# 5v_power_supply.net
KiCad netlist of a schematic drawn in EAGLE
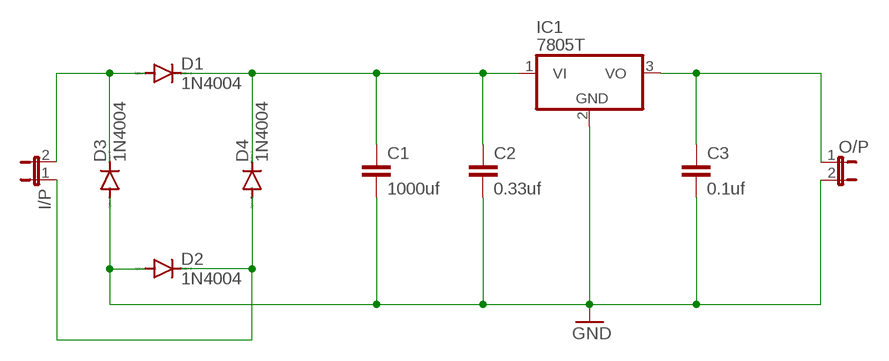
[diagram p0: schematic, sheet 1]

(export (version "E")
  (design (tool "Eeschema 10.0.6"))
  (components
    (comp (ref "C1")
      (value "1000uf")
      (footprint "eagle-import:C2.5-3")
      (libsource (lib "eagle-import") (part "C2,5-3"))
    )
    (comp (ref "C2")
      (value "0.33uf")
      (footprint "eagle-import:C2.5-3")
      (libsource (lib "eagle-import") (part "C2,5-3"))
    )
    (comp (ref "C3")
      (value "0.1uf")
      (footprint "eagle-import:C2.5-3")
      (libsource (lib "eagle-import") (part "C2,5-3"))
    )
    (comp (ref "D1")
      (value "1N4004")
      (footprint "eagle-import:DO41-10")
      (libsource (lib "eagle-import") (part "1N4004"))
    )
    (comp (ref "D2")
      (value "1N4004")
      (footprint "eagle-import:DO41-10")
      (libsource (lib "eagle-import") (part "1N4004"))
    )
    (comp (ref "D3")
      (value "1N4004")
      (footprint "eagle-import:DO41-10")
      (libsource (lib "eagle-import") (part "1N4004"))
    )
    (comp (ref "D4")
      (value "1N4004")
      (footprint "eagle-import:DO41-10")
      (libsource (lib "eagle-import") (part "1N4004"))
    )
    (comp (ref "I/P")
      (value "JP1E")
      (footprint "eagle-import:JP1")
      (libsource (lib "eagle-import") (part "JP1E"))
    )
    (comp (ref "IC1")
      (value "7805T")
      (footprint "eagle-import:TO220H")
      (libsource (lib "eagle-import") (part "78T05"))
    )
    (comp (ref "O/P")
      (value "JP1E")
      (footprint "eagle-import:JP1")
      (libsource (lib "eagle-import") (part "JP1E"))
    )
  )
  (nets
    (net (code "1") (name "GND") (class "Default")
      (node (ref "C1") (pin "2") (pinfunction "2_2") (pintype "passive"))
      (node (ref "C2") (pin "2") (pinfunction "2_2") (pintype "passive"))
      (node (ref "C3") (pin "2") (pinfunction "2_2") (pintype "passive"))
      (node (ref "D2") (pin "A") (pinfunction "A_A") (pintype "passive"))
      (node (ref "D3") (pin "A") (pinfunction "A_A") (pintype "passive"))
      (node (ref "IC1") (pin "2") (pinfunction "GND_2") (pintype "passive"))
      (node (ref "O/P") (pin "2") (pinfunction "2_2") (pintype "passive"))
    )
    (net (code "2") (name "Net-(D1-PadA)") (class "Default")
      (node (ref "D1") (pin "A") (pinfunction "A_A") (pintype "passive"))
      (node (ref "D3") (pin "C") (pinfunction "C_C") (pintype "passive"))
      (node (ref "I/P") (pin "2") (pinfunction "2_2") (pintype "passive"))
    )
    (net (code "3") (name "Net-(D2-PadC)") (class "Default")
      (node (ref "D2") (pin "C") (pinfunction "C_C") (pintype "passive"))
      (node (ref "D4") (pin "A") (pinfunction "A_A") (pintype "passive"))
      (node (ref "I/P") (pin "1") (pinfunction "1_1") (pintype "passive"))
    )
    (net (code "4") (name "Net-(IC1-VI)") (class "Default")
      (node (ref "C1") (pin "1") (pinfunction "1_1") (pintype "passive"))
      (node (ref "C2") (pin "1") (pinfunction "1_1") (pintype "passive"))
      (node (ref "D1") (pin "C") (pinfunction "C_C") (pintype "passive"))
      (node (ref "D4") (pin "C") (pinfunction "C_C") (pintype "passive"))
      (node (ref "IC1") (pin "1") (pinfunction "VI_1") (pintype "input"))
    )
    (net (code "5") (name "Net-(IC1-VO)") (class "Default")
      (node (ref "C3") (pin "1") (pinfunction "1_1") (pintype "passive"))
      (node (ref "IC1") (pin "3") (pinfunction "VO_3") (pintype "passive"))
      (node (ref "O/P") (pin "1") (pinfunction "1_1") (pintype "passive"))
    )
  )
)
